# blds.net
KiCad netlist of a schematic drawn in Altium Designer
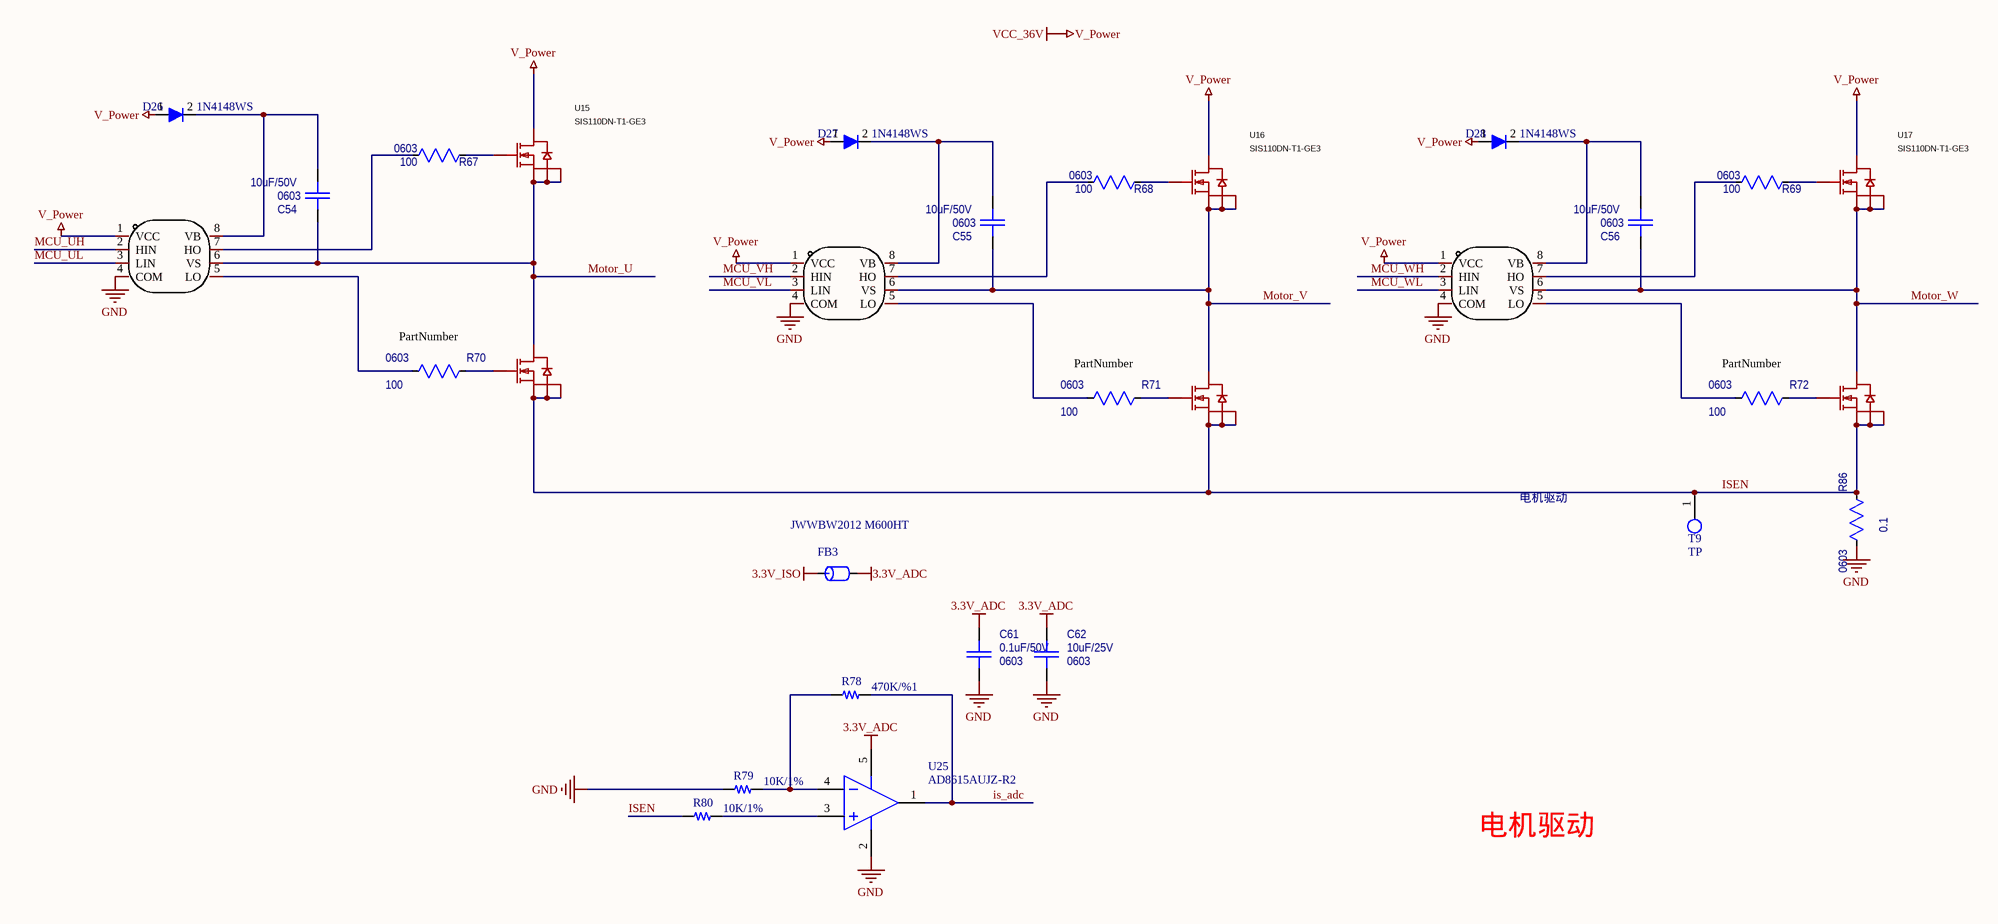
[diagram p0: blds.SchDoc]

(export (version "E")
  (design (tool "Eeschema 10.0.6"))
  (components
    (comp (ref "C54")
      (value "10uF/50V")
      (footprint "CAPC1608X092N_0603")
      (description "Capacitor, MLCC")
      (fields
        (field (name "MANUFACTURER") "muRata")
        (field (name "PARTNUMBER") "GQM2195C2E4R7CB12J")
        (field (name "PACKAGE") "0603")
      )
      (libsource (lib "Karl") (part "Capacitor_0603"))
    )
    (comp (ref "C55")
      (value "10uF/50V")
      (footprint "CAPC1608X092N_0603")
      (description "Capacitor, MLCC")
      (fields
        (field (name "MANUFACTURER") "muRata")
        (field (name "PARTNUMBER") "GQM2195C2E4R7CB12J")
        (field (name "PACKAGE") "0603")
      )
      (libsource (lib "Karl") (part "Capacitor_0603"))
    )
    (comp (ref "C56")
      (value "10uF/50V")
      (footprint "CAPC1608X092N_0603")
      (description "Capacitor, MLCC")
      (fields
        (field (name "MANUFACTURER") "muRata")
        (field (name "PARTNUMBER") "GQM2195C2E4R7CB12J")
        (field (name "PACKAGE") "0603")
      )
      (libsource (lib "Karl") (part "Capacitor_0603"))
    )
    (comp (ref "C61")
      (value "0.1uF/50V")
      (footprint "CAPC1608X092N_0603")
      (fields
        (field (name "PARTNUMBER") "C0603C104M5RACTU")
        (field (name "TOLERANCE") "[tol]")
        (field (name "PACKAGE") "0603")
        (field (name "Comment") "Capacitor_0603")
      )
      (libsource (lib "Karl") (part "Capacitor_0603"))
    )
    (comp (ref "C62")
      (value "10uF/25V")
      (footprint "CAPC1608X092N_0603")
      (fields
        (field (name "PARTNUMBER") "C0603C104M5RACTU")
        (field (name "TOLERANCE") "[tol]")
        (field (name "PACKAGE") "0603")
        (field (name "Comment") "Capacitor_0603")
      )
      (libsource (lib "Karl") (part "Capacitor_0603"))
    )
    (comp (ref "D26") (value "1N4148WS") (footprint "SOD323") (libsource (lib "Device2018") (part "LL4148")))
    (comp (ref "D27") (value "1N4148WS") (footprint "SOD323") (libsource (lib "Device2018") (part "LL4148")))
    (comp (ref "D28") (value "1N4148WS") (footprint "SOD323") (libsource (lib "Device2018") (part "LL4148")))
    (comp (ref "FB3")
      (value "JWWBW2012 M600HT")
      (footprint "0805R")
      (libsource (lib "Schlib_20110825") (part "FB"))
    )
    (comp (ref "R67")
      (value "100")
      (footprint "RESC1608X055N_0603")
      (description "Resistor, Standard")
      (fields
        (field (name "MANUFACTURER") "Yageo")
        (field (name "PARTNUMBER") "RC0603FR-0710KL")
        (field (name "PACKAGE") "0603")
      )
      (libsource (lib "Karl") (part "Resistor_0603"))
    )
    (comp (ref "R68")
      (value "100")
      (footprint "RESC1608X055N_0603")
      (description "Resistor, Standard")
      (fields
        (field (name "MANUFACTURER") "Yageo")
        (field (name "PARTNUMBER") "RC0603FR-0710KL")
        (field (name "PACKAGE") "0603")
      )
      (libsource (lib "Karl") (part "Resistor_0603"))
    )
    (comp (ref "R69")
      (value "100")
      (footprint "RESC1608X055N_0603")
      (description "Resistor, Standard")
      (fields
        (field (name "MANUFACTURER") "Yageo")
        (field (name "PARTNUMBER") "RC0603FR-0710KL")
        (field (name "PACKAGE") "0603")
      )
      (libsource (lib "Karl") (part "Resistor_0603"))
    )
    (comp (ref "R70")
      (value "100")
      (footprint "RESC1608X055N_0603")
      (description "Resistor, Standard")
      (fields
        (field (name "MANUFACTURER") "Yageo")
        (field (name "PARTNUMBER") "RC0603FR-0710KL")
        (field (name "PACKAGE") "0603")
      )
      (libsource (lib "Karl") (part "Resistor_0603"))
    )
    (comp (ref "R71")
      (value "100")
      (footprint "RESC1608X055N_0603")
      (description "Resistor, Standard")
      (fields
        (field (name "MANUFACTURER") "Yageo")
        (field (name "PARTNUMBER") "RC0603FR-0710KL")
        (field (name "PACKAGE") "0603")
      )
      (libsource (lib "Karl") (part "Resistor_0603"))
    )
    (comp (ref "R72")
      (value "100")
      (footprint "RESC1608X055N_0603")
      (description "Resistor, Standard")
      (fields
        (field (name "MANUFACTURER") "Yageo")
        (field (name "PARTNUMBER") "RC0603FR-0710KL")
        (field (name "PACKAGE") "0603")
      )
      (libsource (lib "Karl") (part "Resistor_0603"))
    )
    (comp (ref "R78") (value "470K/%1") (footprint "0603R") (libsource (lib "JRJ_1") (part "R")))
    (comp (ref "R79") (value "10K/1%") (footprint "0603R") (libsource (lib "JRJ_1") (part "R")))
    (comp (ref "R80") (value "10K/1%") (footprint "0603R") (libsource (lib "JRJ_1") (part "R")))
    (comp (ref "R86")
      (value "0.1")
      (footprint "2010R")
      (description "Resistor, Standard")
      (fields
        (field (name "MANUFACTURER") "Yageo")
        (field (name "PARTNUMBER") "RC0603FR-0710KL")
        (field (name "PACKAGE") "0603")
      )
      (libsource (lib "Karl") (part "Resistor_0603"))
    )
    (comp (ref "T9") (value "TP") (footprint "TPD") (libsource (lib "Schlib_20110825") (part "TP")))
    (comp (ref "U15")
      (value "SIS110DN-T1-GE3")
      (footprint "DFN-8_L3.3-W3.3-P0.65-BL-2")
      (fields (field (name "MANUFACTURER") "VISHAY(威世)"))
      (libsource (lib "altium-import") (part "root_0_SIS110DN-T1-GE3_"))
    )
    (comp (ref "U16")
      (value "SIS110DN-T1-GE3")
      (footprint "DFN-8_L3.3-W3.3-P0.65-BL-2")
      (fields (field (name "MANUFACTURER") "VISHAY(威世)"))
      (libsource (lib "altium-import") (part "root_0_SIS110DN-T1-GE3_"))
    )
    (comp (ref "U17")
      (value "SIS110DN-T1-GE3")
      (footprint "DFN-8_L3.3-W3.3-P0.65-BL-2")
      (fields (field (name "MANUFACTURER") "VISHAY(威世)"))
      (libsource (lib "altium-import") (part "root_0_SIS110DN-T1-GE3_"))
    )
    (comp (ref "U18")
      (value "IRS21867STRPBF")
      (footprint "SO-8")
      (fields (field (name "MANUFACTURER") "Infineon(英飞凌)"))
      (libsource (lib "altium-import") (part "root_0_IRS21867STRPBF_"))
    )
    (comp (ref "U19")
      (value "IRS21867STRPBF")
      (footprint "SO-8")
      (fields (field (name "MANUFACTURER") "Infineon(英飞凌)"))
      (libsource (lib "altium-import") (part "root_0_IRS21867STRPBF_"))
    )
    (comp (ref "U20")
      (value "IRS21867STRPBF")
      (footprint "SO-8")
      (fields (field (name "MANUFACTURER") "Infineon(英飞凌)"))
      (libsource (lib "altium-import") (part "root_0_IRS21867STRPBF_"))
    )
    (comp (ref "U21")
      (value "SIS110DN-T1-GE3")
      (footprint "DFN-8_L3.3-W3.3-P0.65-BL-2")
      (fields (field (name "MANUFACTURER") "VISHAY(威世)"))
      (libsource (lib "altium-import") (part "root_0_SIS110DN-T1-GE3_"))
    )
    (comp (ref "U22")
      (value "SIS110DN-T1-GE3")
      (footprint "DFN-8_L3.3-W3.3-P0.65-BL-2")
      (fields (field (name "MANUFACTURER") "VISHAY(威世)"))
      (libsource (lib "altium-import") (part "root_0_SIS110DN-T1-GE3_"))
    )
    (comp (ref "U23")
      (value "SIS110DN-T1-GE3")
      (footprint "DFN-8_L3.3-W3.3-P0.65-BL-2")
      (fields (field (name "MANUFACTURER") "VISHAY(威世)"))
      (libsource (lib "altium-import") (part "root_0_SIS110DN-T1-GE3_"))
    )
    (comp (ref "U25")
      (value "AD8615AUJZ-R2")
      (footprint "sot-23-5")
      (libsource (lib "Schlib_20110825") (part "AD8615"))
    )
  )
  (nets
    (net (code "1") (name "/ISEN") (class "Default")
      (node (ref "R80") (pin "2") (pintype "passive"))
      (node (ref "R86") (pin "2") (pinfunction "2_2") (pintype "passive"))
      (node (ref "T9") (pin "1") (pintype "passive"))
      (node (ref "U21") (pin "1") (pinfunction "S_1") (pintype "passive"))
      (node (ref "U21") (pin "2") (pinfunction "S_2") (pintype "passive"))
      (node (ref "U21") (pin "3") (pinfunction "S_3") (pintype "passive"))
      (node (ref "U22") (pin "1") (pinfunction "S_1") (pintype "passive"))
      (node (ref "U22") (pin "2") (pinfunction "S_2") (pintype "passive"))
      (node (ref "U22") (pin "3") (pinfunction "S_3") (pintype "passive"))
      (node (ref "U23") (pin "1") (pinfunction "S_1") (pintype "passive"))
      (node (ref "U23") (pin "2") (pinfunction "S_2") (pintype "passive"))
      (node (ref "U23") (pin "3") (pinfunction "S_3") (pintype "passive"))
    )
    (net (code "2") (name "/MCU_UH") (class "Default")
      (node (ref "U18") (pin "2") (pinfunction "HIN_2") (pintype "passive"))
    )
    (net (code "3") (name "/MCU_UL") (class "Default")
      (node (ref "U18") (pin "3") (pinfunction "LIN_3") (pintype "passive"))
    )
    (net (code "4") (name "/MCU_VH") (class "Default")
      (node (ref "U19") (pin "2") (pinfunction "HIN_2") (pintype "passive"))
    )
    (net (code "5") (name "/MCU_VL") (class "Default")
      (node (ref "U19") (pin "3") (pinfunction "LIN_3") (pintype "passive"))
    )
    (net (code "6") (name "/MCU_WH") (class "Default")
      (node (ref "U20") (pin "2") (pinfunction "HIN_2") (pintype "passive"))
    )
    (net (code "7") (name "/MCU_WL") (class "Default")
      (node (ref "U20") (pin "3") (pinfunction "LIN_3") (pintype "passive"))
    )
    (net (code "8") (name "/Motor_U") (class "Default")
      (node (ref "C54") (pin "1") (pinfunction "1_1") (pintype "passive"))
      (node (ref "U15") (pin "1") (pinfunction "S_1") (pintype "passive"))
      (node (ref "U15") (pin "2") (pinfunction "S_2") (pintype "passive"))
      (node (ref "U15") (pin "3") (pinfunction "S_3") (pintype "passive"))
      (node (ref "U18") (pin "6") (pinfunction "VS_6") (pintype "passive"))
      (node (ref "U21") (pin "5") (pinfunction "D_5") (pintype "passive"))
    )
    (net (code "9") (name "/Motor_V") (class "Default")
      (node (ref "C55") (pin "1") (pinfunction "1_1") (pintype "passive"))
      (node (ref "U16") (pin "1") (pinfunction "S_1") (pintype "passive"))
      (node (ref "U16") (pin "2") (pinfunction "S_2") (pintype "passive"))
      (node (ref "U16") (pin "3") (pinfunction "S_3") (pintype "passive"))
      (node (ref "U19") (pin "6") (pinfunction "VS_6") (pintype "passive"))
      (node (ref "U22") (pin "5") (pinfunction "D_5") (pintype "passive"))
    )
    (net (code "10") (name "/Motor_W") (class "Default")
      (node (ref "C56") (pin "1") (pinfunction "1_1") (pintype "passive"))
      (node (ref "U17") (pin "1") (pinfunction "S_1") (pintype "passive"))
      (node (ref "U17") (pin "2") (pinfunction "S_2") (pintype "passive"))
      (node (ref "U17") (pin "3") (pinfunction "S_3") (pintype "passive"))
      (node (ref "U20") (pin "6") (pinfunction "VS_6") (pintype "passive"))
      (node (ref "U23") (pin "5") (pinfunction "D_5") (pintype "passive"))
    )
    (net (code "11") (name "/is_adc") (class "Default")
      (node (ref "R78") (pin "1") (pintype "passive"))
      (node (ref "U25") (pin "1") (pinfunction "OS_NUL_1") (pintype "passive"))
    )
    (net (code "12") (name "3.3V_ADC") (class "Default")
      (node (ref "C61") (pin "1") (pinfunction "1_1") (pintype "passive"))
      (node (ref "C62") (pin "1") (pinfunction "1_1") (pintype "passive"))
      (node (ref "FB3") (pin "2") (pintype "passive"))
      (node (ref "U25") (pin "5") (pinfunction "VCC_5") (pintype "passive"))
    )
    (net (code "13") (name "3.3V_ISO") (class "Default") (node (ref "FB3") (pin "1") (pintype "passive")))
    (net (code "14") (name "GND") (class "Default")
      (node (ref "C61") (pin "2") (pinfunction "2_2") (pintype "passive"))
      (node (ref "C62") (pin "2") (pinfunction "2_2") (pintype "passive"))
      (node (ref "R79") (pin "2") (pintype "passive"))
      (node (ref "R86") (pin "1") (pinfunction "1_1") (pintype "passive"))
      (node (ref "U18") (pin "4") (pinfunction "COM_4") (pintype "passive"))
      (node (ref "U19") (pin "4") (pinfunction "COM_4") (pintype "passive"))
      (node (ref "U20") (pin "4") (pinfunction "COM_4") (pintype "passive"))
      (node (ref "U25") (pin "2") (pinfunction "G_2") (pintype "power_in"))
    )
    (net (code "15") (name "Net-(D26-A)") (class "Default")
      (node (ref "C54") (pin "2") (pinfunction "2_2") (pintype "passive"))
      (node (ref "D26") (pin "2") (pinfunction "A_2") (pintype "passive"))
      (node (ref "U18") (pin "8") (pinfunction "VB_8") (pintype "passive"))
    )
    (net (code "16") (name "Net-(D27-A)") (class "Default")
      (node (ref "C55") (pin "2") (pinfunction "2_2") (pintype "passive"))
      (node (ref "D27") (pin "2") (pinfunction "A_2") (pintype "passive"))
      (node (ref "U19") (pin "8") (pinfunction "VB_8") (pintype "passive"))
    )
    (net (code "17") (name "Net-(D28-A)") (class "Default")
      (node (ref "C56") (pin "2") (pinfunction "2_2") (pintype "passive"))
      (node (ref "D28") (pin "2") (pinfunction "A_2") (pintype "passive"))
      (node (ref "U20") (pin "8") (pinfunction "VB_8") (pintype "passive"))
    )
    (net (code "18") (name "Net-(U15-G)") (class "Default")
      (node (ref "R67") (pin "2") (pinfunction "2_2") (pintype "passive"))
      (node (ref "U15") (pin "4") (pinfunction "G_4") (pintype "passive"))
    )
    (net (code "19") (name "Net-(U16-G)") (class "Default")
      (node (ref "R68") (pin "2") (pinfunction "2_2") (pintype "passive"))
      (node (ref "U16") (pin "4") (pinfunction "G_4") (pintype "passive"))
    )
    (net (code "20") (name "Net-(U17-G)") (class "Default")
      (node (ref "R69") (pin "2") (pinfunction "2_2") (pintype "passive"))
      (node (ref "U17") (pin "4") (pinfunction "G_4") (pintype "passive"))
    )
    (net (code "21") (name "Net-(U18-HO)") (class "Default")
      (node (ref "R67") (pin "1") (pinfunction "1_1") (pintype "passive"))
      (node (ref "U18") (pin "7") (pinfunction "HO_7") (pintype "passive"))
    )
    (net (code "22") (name "Net-(U18-LO)") (class "Default")
      (node (ref "R70") (pin "1") (pinfunction "1_1") (pintype "passive"))
      (node (ref "U18") (pin "5") (pinfunction "LO_5") (pintype "passive"))
    )
    (net (code "23") (name "Net-(U19-HO)") (class "Default")
      (node (ref "R68") (pin "1") (pinfunction "1_1") (pintype "passive"))
      (node (ref "U19") (pin "7") (pinfunction "HO_7") (pintype "passive"))
    )
    (net (code "24") (name "Net-(U19-LO)") (class "Default")
      (node (ref "R71") (pin "1") (pinfunction "1_1") (pintype "passive"))
      (node (ref "U19") (pin "5") (pinfunction "LO_5") (pintype "passive"))
    )
    (net (code "25") (name "Net-(U20-HO)") (class "Default")
      (node (ref "R69") (pin "1") (pinfunction "1_1") (pintype "passive"))
      (node (ref "U20") (pin "7") (pinfunction "HO_7") (pintype "passive"))
    )
    (net (code "26") (name "Net-(U20-LO)") (class "Default")
      (node (ref "R72") (pin "1") (pinfunction "1_1") (pintype "passive"))
      (node (ref "U20") (pin "5") (pinfunction "LO_5") (pintype "passive"))
    )
    (net (code "27") (name "Net-(U21-G)") (class "Default")
      (node (ref "R70") (pin "2") (pinfunction "2_2") (pintype "passive"))
      (node (ref "U21") (pin "4") (pinfunction "G_4") (pintype "passive"))
    )
    (net (code "28") (name "Net-(U22-G)") (class "Default")
      (node (ref "R71") (pin "2") (pinfunction "2_2") (pintype "passive"))
      (node (ref "U22") (pin "4") (pinfunction "G_4") (pintype "passive"))
    )
    (net (code "29") (name "Net-(U23-G)") (class "Default")
      (node (ref "R72") (pin "2") (pinfunction "2_2") (pintype "passive"))
      (node (ref "U23") (pin "4") (pinfunction "G_4") (pintype "passive"))
    )
    (net (code "30") (name "Net-(U25-V+)") (class "Default")
      (node (ref "R80") (pin "1") (pintype "passive"))
      (node (ref "U25") (pin "3") (pinfunction "V+_3") (pintype "power_in"))
    )
    (net (code "31") (name "Net-(U25-V-)") (class "Default")
      (node (ref "R78") (pin "2") (pintype "passive"))
      (node (ref "R79") (pin "1") (pintype "passive"))
      (node (ref "U25") (pin "4") (pinfunction "V-_4") (pintype "power_in"))
    )
    (net (code "32") (name "VCC_36V") (class "Default")
      (node (ref "D26") (pin "1") (pinfunction "K_1") (pintype "passive"))
      (node (ref "D27") (pin "1") (pinfunction "K_1") (pintype "passive"))
      (node (ref "D28") (pin "1") (pinfunction "K_1") (pintype "passive"))
      (node (ref "U15") (pin "5") (pinfunction "D_5") (pintype "passive"))
      (node (ref "U16") (pin "5") (pinfunction "D_5") (pintype "passive"))
      (node (ref "U17") (pin "5") (pinfunction "D_5") (pintype "passive"))
      (node (ref "U18") (pin "1") (pinfunction "VCC_1") (pintype "passive"))
      (node (ref "U19") (pin "1") (pinfunction "VCC_1") (pintype "passive"))
      (node (ref "U20") (pin "1") (pinfunction "VCC_1") (pintype "passive"))
    )
  )
)
